# Deathsound_preamp_channel.net
KiCad netlist of a schematic drawn in Altium Designer
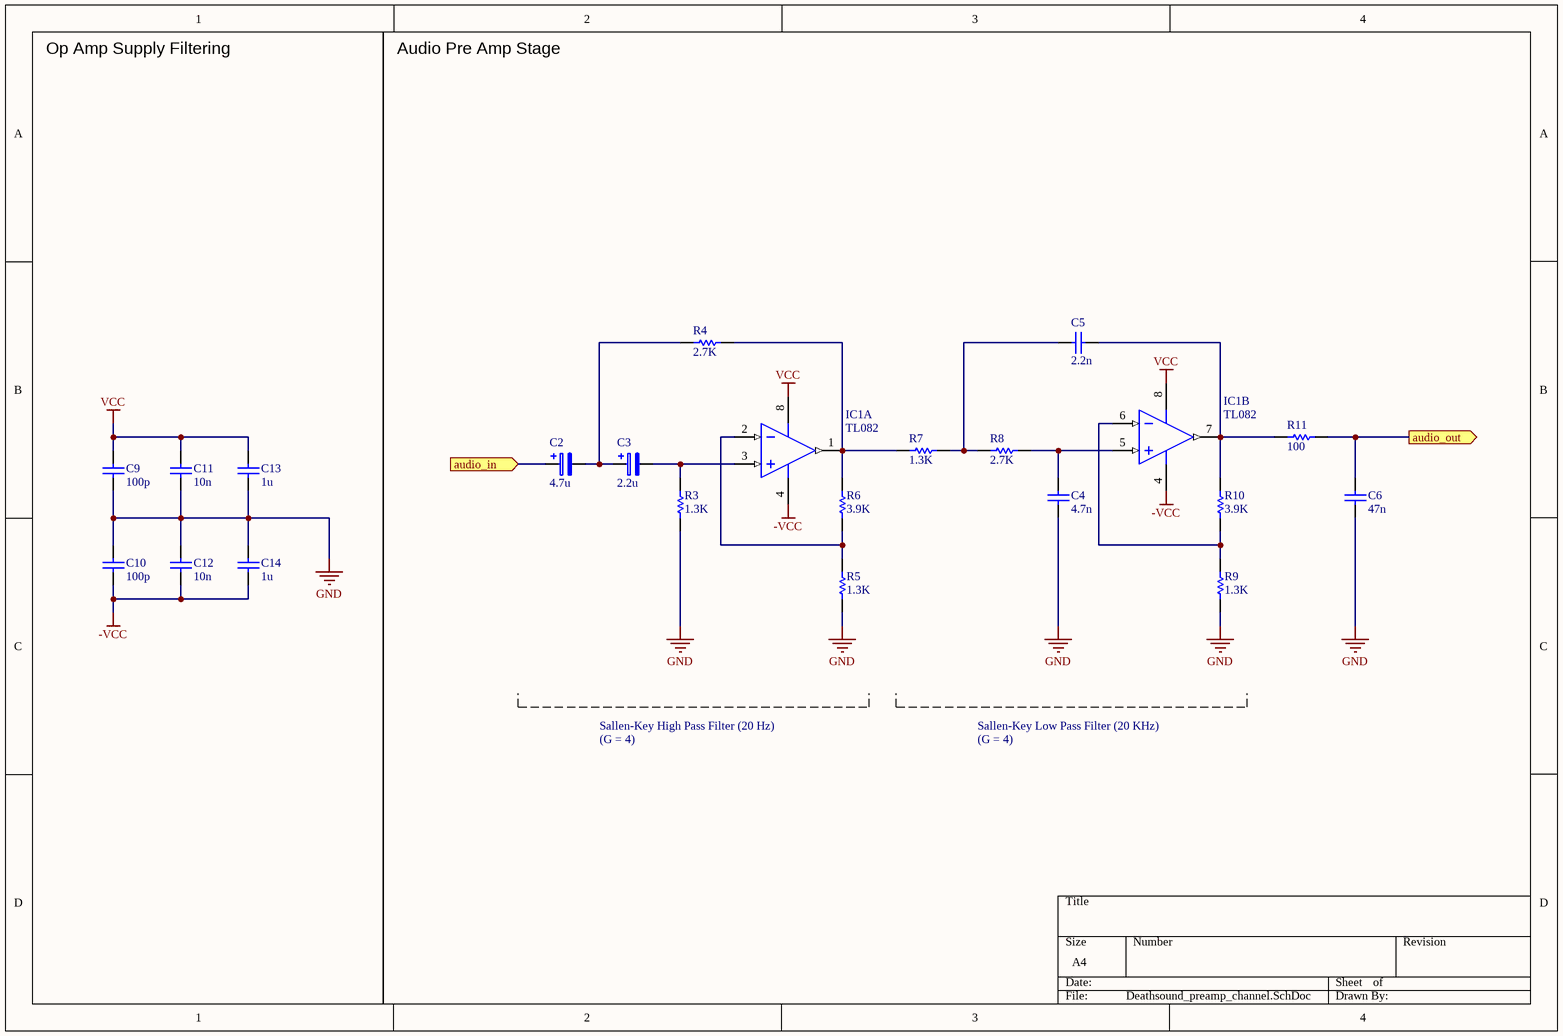
[diagram p0: Deathsound_preamp_channel.SchDoc]

(export (version "E")
  (design (tool "Eeschema 10.0.6"))
  (components
    (comp (ref "C2")
      (value "4.7u")
      (footprint "CRADIAL-2mm")
      (description "Polarized Capacitor")
      (libsource (lib "nucleoduro_lib_audio") (part "Pol Capacitor"))
    )
    (comp (ref "C3")
      (value "2.2u")
      (footprint "CRADIAL-2mm")
      (description "Polarized Capacitor")
      (libsource (lib "nucleoduro_lib_audio") (part "Pol Capacitor"))
    )
    (comp (ref "C4")
      (value "4.7n")
      (footprint "C0805")
      (description "Capacitor")
      (libsource (lib "nucleoduro_lib_audio") (part "Capacitor"))
    )
    (comp (ref "C5")
      (value "2.2n")
      (footprint "C0805")
      (description "Capacitor")
      (libsource (lib "nucleoduro_lib_audio") (part "Capacitor"))
    )
    (comp (ref "C6")
      (value "47n")
      (footprint "C1206")
      (description "Capacitor")
      (libsource (lib "nucleoduro_lib_audio") (part "Capacitor"))
    )
    (comp (ref "C9")
      (value "100p")
      (footprint "C0805")
      (description "Capacitor")
      (libsource (lib "nucleoduro_lib_audio") (part "Capacitor"))
    )
    (comp (ref "C10")
      (value "100p")
      (footprint "C0805")
      (description "Capacitor")
      (libsource (lib "nucleoduro_lib_audio") (part "Capacitor"))
    )
    (comp (ref "C11")
      (value "10n")
      (footprint "C0805")
      (description "Capacitor")
      (libsource (lib "nucleoduro_lib_audio") (part "Capacitor"))
    )
    (comp (ref "C12")
      (value "10n")
      (footprint "C0805")
      (description "Capacitor")
      (libsource (lib "nucleoduro_lib_audio") (part "Capacitor"))
    )
    (comp (ref "C13")
      (value "1u")
      (footprint "C0805")
      (description "Capacitor")
      (libsource (lib "nucleoduro_lib_audio") (part "Capacitor"))
    )
    (comp (ref "C14")
      (value "1u")
      (footprint "C0805")
      (description "Capacitor")
      (libsource (lib "nucleoduro_lib_audio") (part "Capacitor"))
    )
    (comp (ref "IC1")
      (value "TL082")
      (footprint "SOIC127P600X175-8N")
      (libsource (lib "nucleoduro_lib_audio") (part "TL082"))
    )
    (comp (ref "R3")
      (value "1.3K")
      (footprint "R0805")
      (description "Resistor")
      (libsource (lib "nucleoduro_lib_audio") (part "Resistor"))
    )
    (comp (ref "R4")
      (value "2.7K")
      (footprint "R0805")
      (description "Resistor")
      (libsource (lib "nucleoduro_lib_audio") (part "Resistor"))
    )
    (comp (ref "R5")
      (value "1.3K")
      (footprint "R0805")
      (description "Resistor")
      (libsource (lib "nucleoduro_lib_audio") (part "Resistor"))
    )
    (comp (ref "R6")
      (value "3.9K")
      (footprint "R0805")
      (description "Resistor")
      (libsource (lib "nucleoduro_lib_audio") (part "Resistor"))
    )
    (comp (ref "R7")
      (value "1.3K")
      (footprint "R0805")
      (description "Resistor")
      (libsource (lib "nucleoduro_lib_audio") (part "Resistor"))
    )
    (comp (ref "R8")
      (value "2.7K")
      (footprint "R0805")
      (description "Resistor")
      (libsource (lib "nucleoduro_lib_audio") (part "Resistor"))
    )
    (comp (ref "R9")
      (value "1.3K")
      (footprint "R0805")
      (description "Resistor")
      (libsource (lib "nucleoduro_lib_audio") (part "Resistor"))
    )
    (comp (ref "R10")
      (value "3.9K")
      (footprint "R0805")
      (description "Resistor")
      (libsource (lib "nucleoduro_lib_audio") (part "Resistor"))
    )
    (comp (ref "R11")
      (value "100")
      (footprint "R0805")
      (description "Resistor")
      (libsource (lib "nucleoduro_lib_audio") (part "Resistor"))
    )
  )
  (nets
    (net (code "1") (name "-VCC") (class "Default")
      (node (ref "C10") (pin "1") (pinfunction "1_1") (pintype "passive"))
      (node (ref "C12") (pin "1") (pinfunction "1_1") (pintype "passive"))
      (node (ref "C14") (pin "1") (pinfunction "1_1") (pintype "passive"))
      (node (ref "IC1") (pin "4") (pinfunction "V-_4") (pintype "power_in"))
    )
    (net (code "2") (name "/audio_in") (class "Default")
      (node (ref "C2") (pin "1") (pinfunction "1_1") (pintype "passive"))
    )
    (net (code "3") (name "/audio_out") (class "Default")
      (node (ref "C6") (pin "2") (pinfunction "2_2") (pintype "passive"))
      (node (ref "R11") (pin "1") (pinfunction "1_1") (pintype "passive"))
    )
    (net (code "4") (name "GND") (class "Default")
      (node (ref "C10") (pin "2") (pinfunction "2_2") (pintype "passive"))
      (node (ref "C11") (pin "1") (pinfunction "1_1") (pintype "passive"))
      (node (ref "C12") (pin "2") (pinfunction "2_2") (pintype "passive"))
      (node (ref "C13") (pin "1") (pinfunction "1_1") (pintype "passive"))
      (node (ref "C14") (pin "2") (pinfunction "2_2") (pintype "passive"))
      (node (ref "C4") (pin "1") (pinfunction "1_1") (pintype "passive"))
      (node (ref "C6") (pin "1") (pinfunction "1_1") (pintype "passive"))
      (node (ref "C9") (pin "1") (pinfunction "1_1") (pintype "passive"))
      (node (ref "R3") (pin "1") (pinfunction "1_1") (pintype "passive"))
      (node (ref "R5") (pin "2") (pinfunction "2_2") (pintype "passive"))
      (node (ref "R9") (pin "1") (pinfunction "1_1") (pintype "passive"))
    )
    (net (code "5") (name "Net-(C2-Pad2)") (class "Default")
      (node (ref "C2") (pin "2") (pinfunction "2_2") (pintype "passive"))
      (node (ref "C3") (pin "1") (pinfunction "1_1") (pintype "passive"))
      (node (ref "R4") (pin "2") (pinfunction "2_2") (pintype "passive"))
    )
    (net (code "6") (name "Net-(C5-Pad2)") (class "Default")
      (node (ref "C5") (pin "2") (pinfunction "2_2") (pintype "passive"))
      (node (ref "R7") (pin "2") (pinfunction "2_2") (pintype "passive"))
      (node (ref "R8") (pin "1") (pinfunction "1_1") (pintype "passive"))
    )
    (net (code "7") (name "Net-(IC1A-IN+1)") (class "Default")
      (node (ref "C3") (pin "2") (pinfunction "2_2") (pintype "passive"))
      (node (ref "IC1") (pin "3") (pinfunction "IN+1_3") (pintype "input"))
      (node (ref "R3") (pin "2") (pinfunction "2_2") (pintype "passive"))
    )
    (net (code "8") (name "Net-(IC1A-IN-1)") (class "Default")
      (node (ref "IC1") (pin "2") (pinfunction "IN-1_2") (pintype "input"))
      (node (ref "R5") (pin "1") (pinfunction "1_1") (pintype "passive"))
      (node (ref "R6") (pin "2") (pinfunction "2_2") (pintype "passive"))
    )
    (net (code "9") (name "Net-(IC1A-OUT1)") (class "Default")
      (node (ref "IC1") (pin "1") (pinfunction "OUT1_1") (pintype "output"))
      (node (ref "R4") (pin "1") (pinfunction "1_1") (pintype "passive"))
      (node (ref "R6") (pin "1") (pinfunction "1_1") (pintype "passive"))
      (node (ref "R7") (pin "1") (pinfunction "1_1") (pintype "passive"))
    )
    (net (code "10") (name "Net-(IC1B-IN+2)") (class "Default")
      (node (ref "C4") (pin "2") (pinfunction "2_2") (pintype "passive"))
      (node (ref "IC1") (pin "5") (pinfunction "IN+2_5") (pintype "input"))
      (node (ref "R8") (pin "2") (pinfunction "2_2") (pintype "passive"))
    )
    (net (code "11") (name "Net-(IC1B-IN-2)") (class "Default")
      (node (ref "IC1") (pin "6") (pinfunction "IN-2_6") (pintype "input"))
      (node (ref "R10") (pin "1") (pinfunction "1_1") (pintype "passive"))
      (node (ref "R9") (pin "2") (pinfunction "2_2") (pintype "passive"))
    )
    (net (code "12") (name "Net-(IC1B-OUT2)") (class "Default")
      (node (ref "C5") (pin "1") (pinfunction "1_1") (pintype "passive"))
      (node (ref "IC1") (pin "7") (pinfunction "OUT2_7") (pintype "output"))
      (node (ref "R10") (pin "2") (pinfunction "2_2") (pintype "passive"))
      (node (ref "R11") (pin "2") (pinfunction "2_2") (pintype "passive"))
    )
    (net (code "13") (name "VCC") (class "Default")
      (node (ref "C11") (pin "2") (pinfunction "2_2") (pintype "passive"))
      (node (ref "C13") (pin "2") (pinfunction "2_2") (pintype "passive"))
      (node (ref "C9") (pin "2") (pinfunction "2_2") (pintype "passive"))
      (node (ref "IC1") (pin "8") (pinfunction "V+_8") (pintype "power_in"))
    )
  )
)
